# LB_BIT_o15_UV_LED-v03_rev1.net
KiCad netlist of a schematic drawn in EAGLE
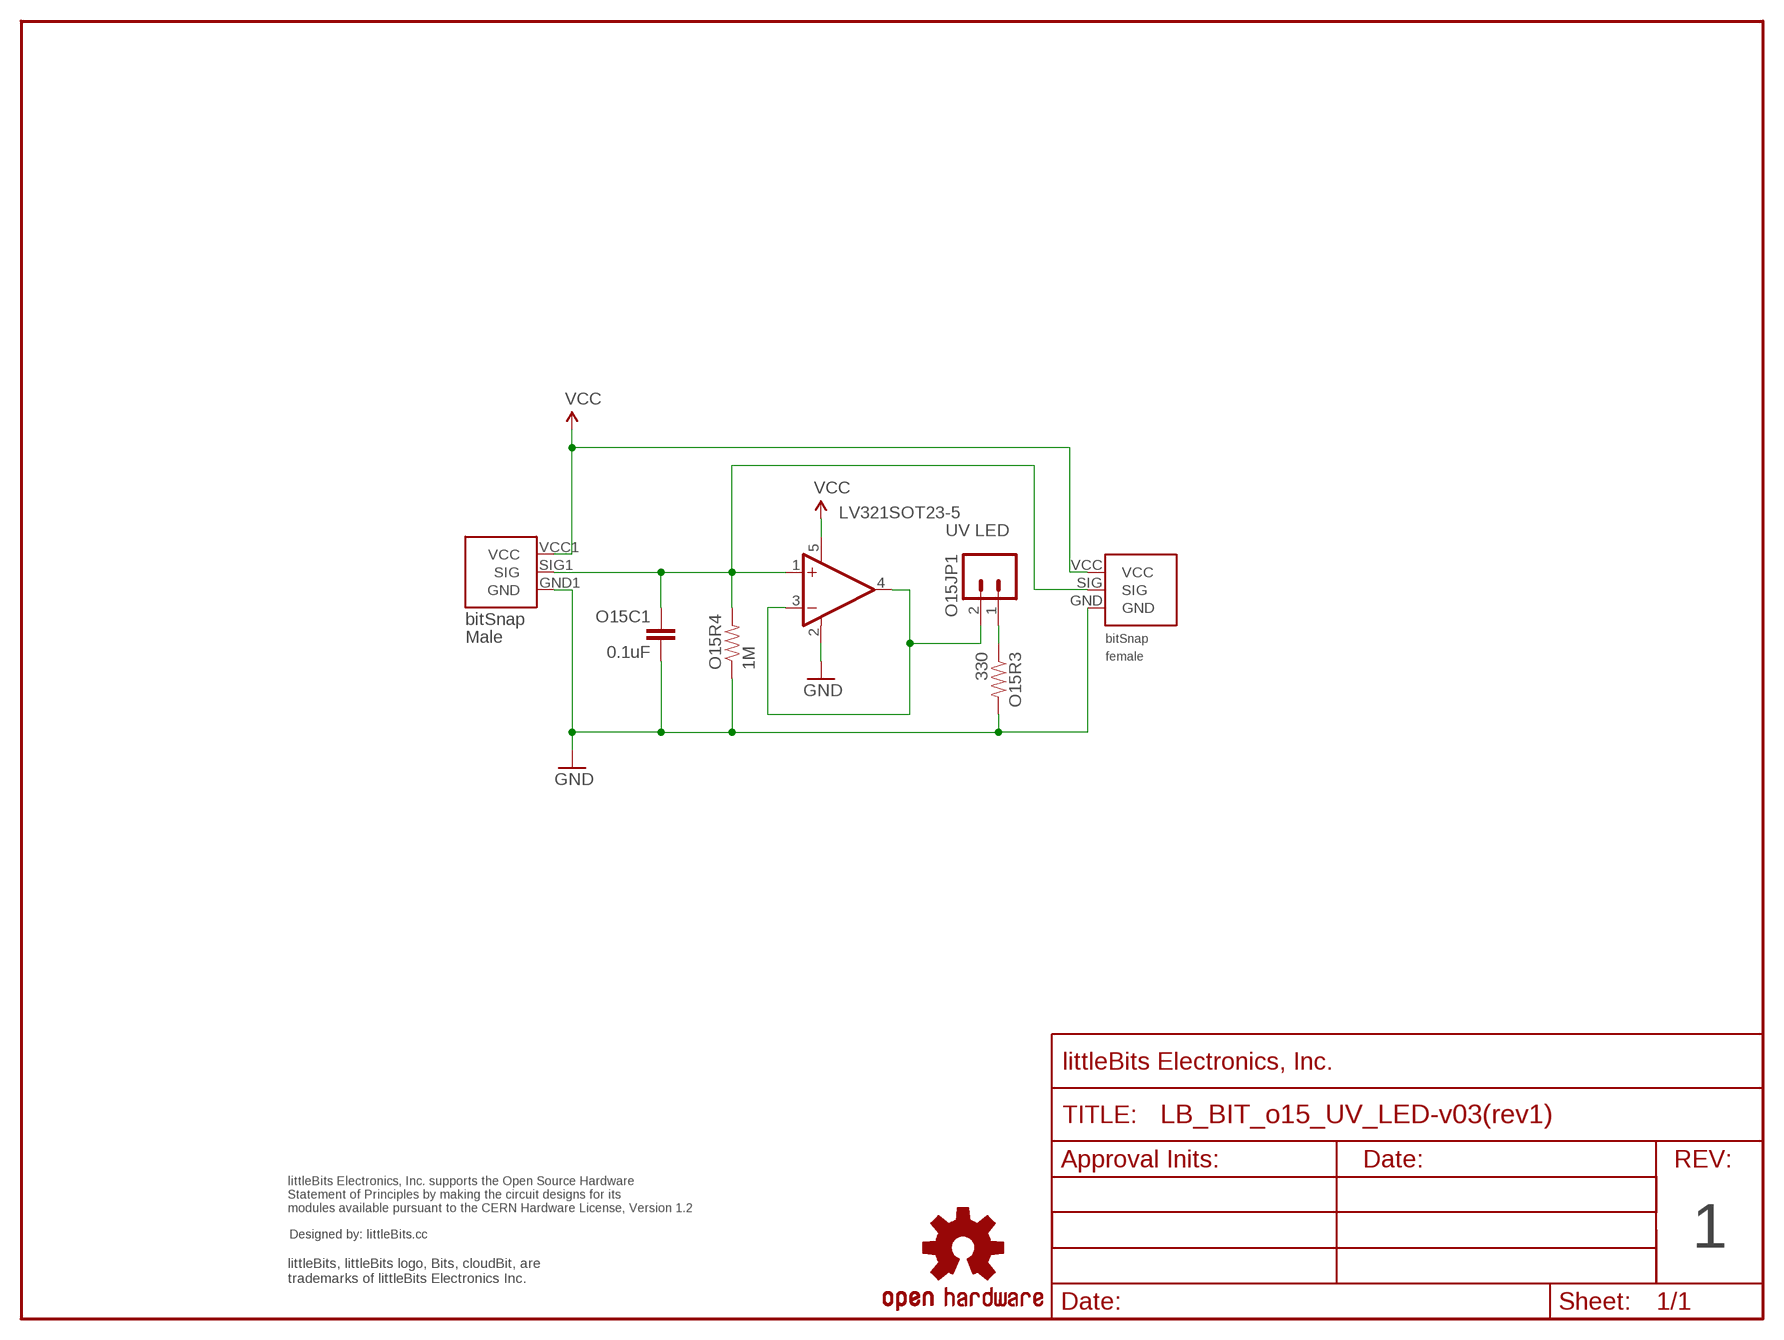
[diagram p0: schematic, sheet 1]

(export (version "E")
  (design (tool "Eeschema 10.0.6"))
  (components
    (comp (ref "O15BSF1")
      (value "BITSNAP_V03_FEMALE")
      (footprint "eagle-import:BITSNAP_V03_FEMALE")
      (libsource (lib "eagle-import") (part "BITSNAP_V03_FEMALE"))
    )
    (comp (ref "O15BSM1")
      (value "BITSNAP_V03_MALE")
      (footprint "eagle-import:BITSNAP_V03_MALE")
      (libsource (lib "eagle-import") (part "BITSNAP_V03_MALE"))
    )
    (comp (ref "O15C1")
      (value "0.1uF")
      (footprint "eagle-import:0603-CAP")
      (libsource (lib "eagle-import") (part "CAP0603-CAP"))
    )
    (comp (ref "O15JP1")
      (value "M02-JST-2MM-SMT")
      (footprint "eagle-import:S2B-PH")
      (libsource (lib "eagle-import") (part "M02-JST-2MM-SMT"))
    )
    (comp (ref "O15R3")
      (value "330")
      (footprint "eagle-import:0603-RES")
      (libsource (lib "eagle-import") (part "RESISTOR0603-RES"))
    )
    (comp (ref "O15R4")
      (value "1M")
      (footprint "eagle-import:0603-RES")
      (libsource (lib "eagle-import") (part "RESISTOR0603-RES"))
    )
    (comp (ref "O15U1")
      (value "LV321SOT23-5")
      (footprint "eagle-import:SOT23-5")
      (libsource (lib "eagle-import") (part "LV321SOT23-5"))
    )
    (comp (ref "U$1")
      (value "FRAME-LETTER-OHWOHW")
      (footprint "eagle-import:FABDWG01-OHW")
      (libsource (lib "eagle-import") (part "FRAME-LETTER-OHWOHW"))
    )
    (comp (ref "U$3")
      (value "OSHW-LOGOL")
      (footprint "eagle-import:OSHW-LOGO-L")
      (libsource (lib "eagle-import") (part "OSHW-LOGOL"))
    )
    (comp (ref "U$4")
      (value "OSHWCREDIT")
      (footprint "eagle-import:OSHWCREDIT")
      (libsource (lib "eagle-import") (part "OSHWCREDIT"))
    )
  )
  (nets
    (net (code "1") (name "GND") (class "Default")
      (node (ref "O15BSF1") (pin "GND") (pinfunction "GND_GND") (pintype "bidirectional"))
      (node (ref "O15BSM1") (pin "GND1") (pinfunction "GND_GND1") (pintype "bidirectional"))
      (node (ref "O15C1") (pin "2") (pinfunction "2_2") (pintype "passive"))
      (node (ref "O15R3") (pin "2") (pinfunction "2_2") (pintype "passive"))
      (node (ref "O15R4") (pin "1") (pinfunction "1_1") (pintype "passive"))
      (node (ref "O15U1") (pin "2") (pinfunction "V-_2") (pintype "power_in"))
    )
    (net (code "2") (name "Net-(O15BSM1-SIG)") (class "Default")
      (node (ref "O15BSF1") (pin "SIG") (pinfunction "SIG_SIG") (pintype "bidirectional"))
      (node (ref "O15BSM1") (pin "SIG1") (pinfunction "SIG_SIG1") (pintype "bidirectional"))
      (node (ref "O15C1") (pin "1") (pinfunction "1_1") (pintype "passive"))
      (node (ref "O15R4") (pin "2") (pinfunction "2_2") (pintype "passive"))
      (node (ref "O15U1") (pin "1") (pinfunction "+IN_1") (pintype "input"))
    )
    (net (code "3") (name "Net-(O15JP1-Pad1)") (class "Default")
      (node (ref "O15JP1") (pin "1") (pinfunction "1_1") (pintype "passive"))
      (node (ref "O15R3") (pin "1") (pinfunction "1_1") (pintype "passive"))
    )
    (net (code "4") (name "Net-(O15U1--IN)") (class "Default")
      (node (ref "O15JP1") (pin "2") (pinfunction "2_2") (pintype "passive"))
      (node (ref "O15U1") (pin "3") (pinfunction "-IN_3") (pintype "input"))
      (node (ref "O15U1") (pin "4") (pinfunction "OUT_4") (pintype "output"))
    )
    (net (code "5") (name "VCC") (class "Default")
      (node (ref "O15BSF1") (pin "VCC") (pinfunction "VCC_VCC") (pintype "bidirectional"))
      (node (ref "O15BSM1") (pin "VCC1") (pinfunction "VCC_VCC1") (pintype "bidirectional"))
      (node (ref "O15U1") (pin "5") (pinfunction "V+_5") (pintype "power_in"))
    )
  )
)
